# 3_0.net
KiCad netlist of a schematic drawn in EasyEDA Pro
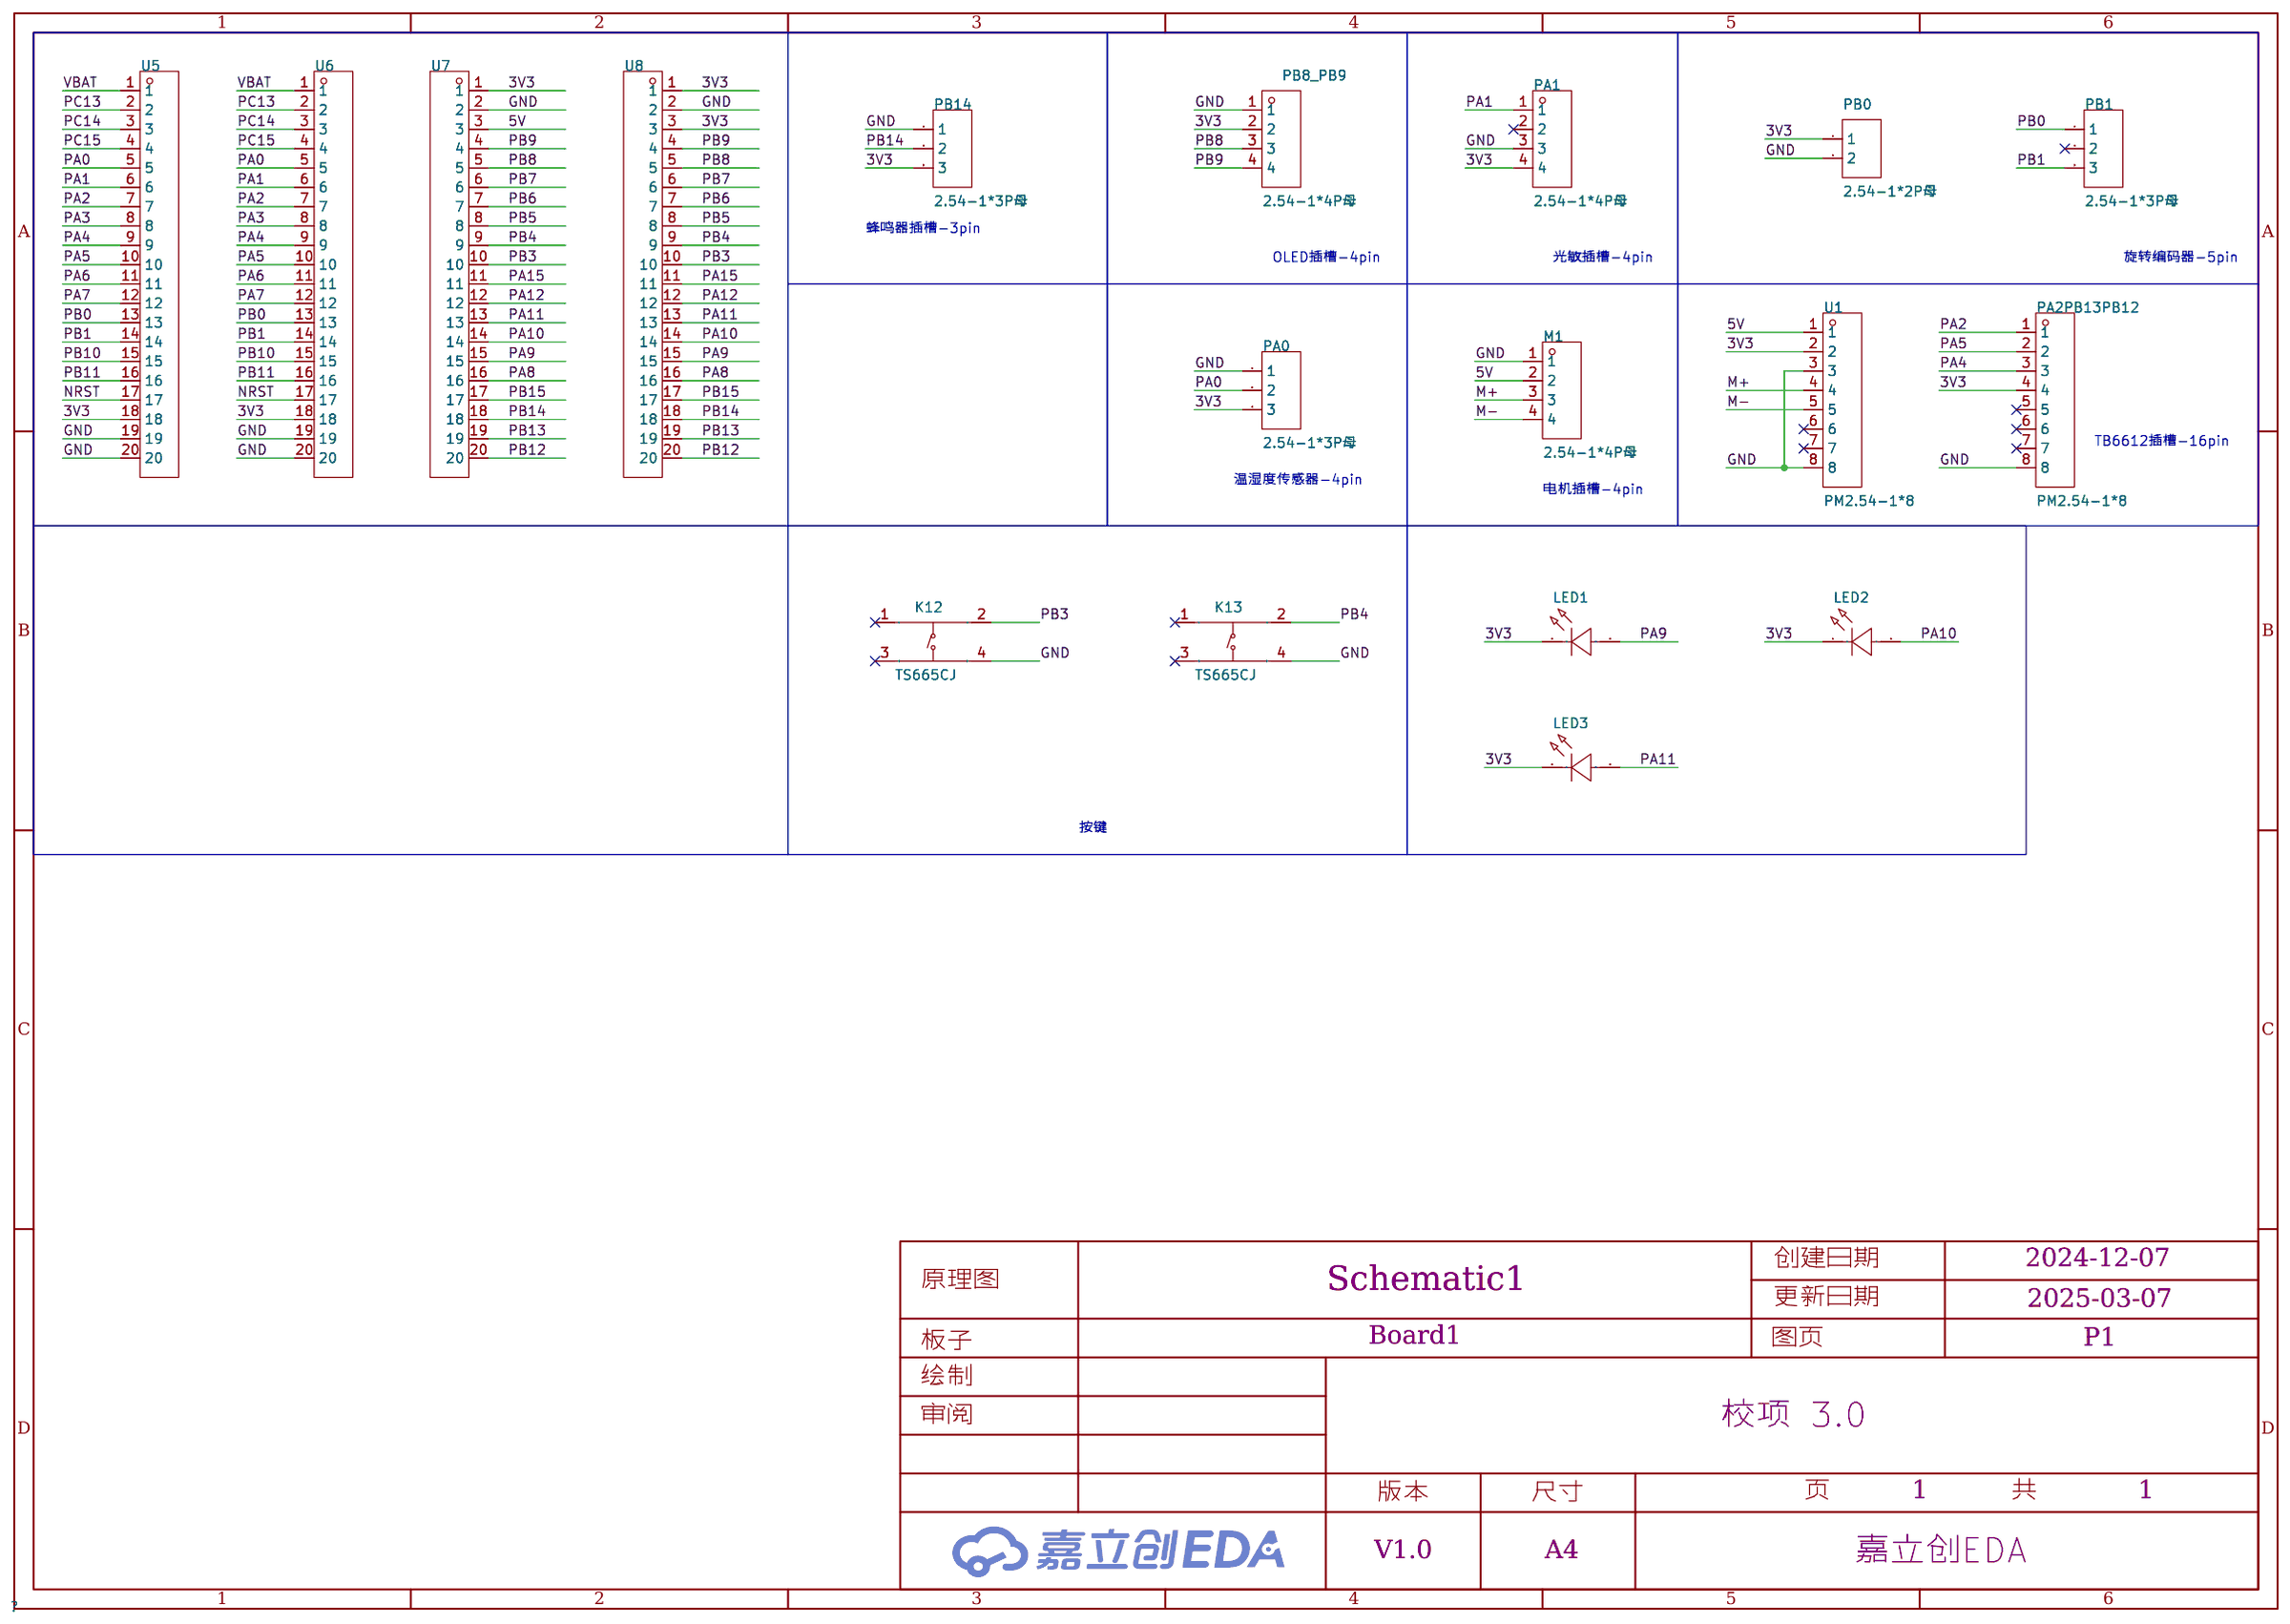
[diagram p0: schematic sheet]

(export (version "E")
  (design (tool "Eeschema 10.0.6"))
  (components
    (comp (ref "K12")
      (value "TS665CJ")
      (footprint "easyedapro:SW-TH_4P-L6.0-W6.0-P4.50-LS6.5")
      (description "电路结构:单刀单掷;按钮形状:圆形按钮;安装方式:直插;开关长度:6mm;开关宽度:6mm;开关高度:5mm;触点电流:50mA;额定电压(DC):12V;带灯:-;机械寿命:-;")
      (fields (field (name "Manufacturer") "SHOU HAN(首韩)"))
      (libsource (lib "easyedapro") (part "TS665CJ"))
    )
    (comp (ref "K13")
      (value "TS665CJ")
      (footprint "easyedapro:SW-TH_4P-L6.0-W6.0-P4.50-LS6.5")
      (description "电路结构:单刀单掷;按钮形状:圆形按钮;安装方式:直插;开关长度:6mm;开关宽度:6mm;开关高度:5mm;触点电流:50mA;额定电压(DC):12V;带灯:-;机械寿命:-;")
      (fields (field (name "Manufacturer") "SHOU HAN(首韩)"))
      (libsource (lib "easyedapro") (part "TS665CJ"))
    )
    (comp (ref "LED1")
      (value "NFD5408BC")
      (footprint "easyedapro:LED-TH_BD5.7-P2.54-RD")
      (description "发光颜色:蓝色;功率:200mW;主波长:460nm~470nm;发光角度:20°;工作温度:-30°C~+85°C;")
      (fields (field (name "Manufacturer") "国星光电"))
      (libsource (lib "easyedapro") (part "NFD5408BC"))
    )
    (comp (ref "LED2")
      (value "NFD5408BC")
      (footprint "easyedapro:LED-TH_BD5.7-P2.54-RD")
      (description "发光颜色:蓝色;功率:200mW;主波长:460nm~470nm;发光角度:20°;工作温度:-30°C~+85°C;")
      (fields (field (name "Manufacturer") "国星光电"))
      (libsource (lib "easyedapro") (part "NFD5408BC"))
    )
    (comp (ref "LED3")
      (value "NFD5408BC")
      (footprint "easyedapro:LED-TH_BD5.7-P2.54-RD")
      (description "发光颜色:蓝色;功率:200mW;主波长:460nm~470nm;发光角度:20°;工作温度:-30°C~+85°C;")
      (fields (field (name "Manufacturer") "国星光电"))
      (libsource (lib "easyedapro") (part "NFD5408BC"))
    )
    (comp (ref "M1")
      (value "2.54-1*4P母")
      (footprint "easyedapro:HDR-TH_4P-P2.54-V-F")
      (fields (field (name "Manufacturer") "BOOMELE(博穆精密)"))
      (libsource (lib "easyedapro") (part "2.54-1*4P母"))
    )
    (comp (ref "PA0")
      (value "2.54-1*3P母")
      (footprint "easyedapro:HDR-TH_3P-P2.54-V-F")
      (description "间距:2.54mm;行距:-;安装类型:直插;排数:单排;总孔位数:3P;塑高:-;触头材质:-;触头镀层:金;")
      (fields (field (name "Manufacturer") "BOOMELE(博穆精密)"))
      (libsource (lib "easyedapro") (part "Header-Female-2.54_1x3"))
    )
    (comp (ref "PA1")
      (value "2.54-1*4P母")
      (footprint "easyedapro:HDR-TH_4P-P2.54-V-F")
      (fields (field (name "Manufacturer") "BOOMELE(博穆精密)"))
      (libsource (lib "easyedapro") (part "2.54-1*4P母"))
    )
    (comp (ref "PA2PB13PB12")
      (value "PM2.54-1*8")
      (footprint "easyedapro:HDR-TH_8P-P2.54-V-F")
      (fields (field (name "Manufacturer") "ZHOURI(洲日)"))
      (libsource (lib "easyedapro") (part "PM2.54-1*8"))
    )
    (comp (ref "PB0")
      (value "2.54-1*2P母")
      (footprint "easyedapro:HDR-TH_2P-P2.54-V-F")
      (description "插孔结构:1x2P;间距:2.54mm;行距:-;安装类型:直插;排数:单排;总孔位数:2P;塑高:-;触头材质:-;触头镀层:-;")
      (fields (field (name "Manufacturer") "BOOMELE(博穆精密)"))
      (libsource (lib "easyedapro") (part "Header-Female-2.54_1x2"))
    )
    (comp (ref "PB1")
      (value "2.54-1*3P母")
      (footprint "easyedapro:HDR-TH_3P-P2.54-V-F")
      (description "间距:2.54mm;行距:-;安装类型:直插;排数:单排;总孔位数:3P;塑高:-;触头材质:-;触头镀层:金;")
      (fields (field (name "Manufacturer") "BOOMELE(博穆精密)"))
      (libsource (lib "easyedapro") (part "Header-Female-2.54_1x3"))
    )
    (comp (ref "PB8_PB9")
      (value "2.54-1*4P母")
      (footprint "easyedapro:HDR-TH_4P-P2.54-V-F")
      (fields (field (name "Manufacturer") "BOOMELE(博穆精密)"))
      (libsource (lib "easyedapro") (part "2.54-1*4P母"))
    )
    (comp (ref "PB14")
      (value "2.54-1*3P母")
      (footprint "easyedapro:HDR-TH_3P-P2.54-V-F")
      (description "间距:2.54mm;行距:-;安装类型:直插;排数:单排;总孔位数:3P;塑高:-;触头材质:-;触头镀层:金;")
      (fields (field (name "Manufacturer") "BOOMELE(博穆精密)"))
      (libsource (lib "easyedapro") (part "Header-Female-2.54_1x3"))
    )
    (comp (ref "U1")
      (value "PM2.54-1*8")
      (footprint "easyedapro:HDR-TH_8P-P2.54-V-F")
      (fields (field (name "Manufacturer") "ZHOURI(洲日)"))
      (libsource (lib "easyedapro") (part "PM2.54-1*8"))
    )
    (comp (ref "U5")
      (value "KH-2.54FH-1X20P-H8.5")
      (footprint "easyedapro:HDR-TH_20P-P2.54-V-F-2")
      (fields (field (name "Manufacturer") "kinghelm(金航标)"))
      (libsource (lib "easyedapro") (part "KH-2.54FH-1X20P-H8.5"))
    )
    (comp (ref "U6")
      (value "KH-2.54FH-1X20P-H8.5")
      (footprint "easyedapro:HDR-TH_20P-P2.54-V-F-2")
      (fields (field (name "Manufacturer") "kinghelm(金航标)"))
      (libsource (lib "easyedapro") (part "KH-2.54FH-1X20P-H8.5"))
    )
    (comp (ref "U7")
      (value "KH-2.54FH-1X20P-H8.5")
      (footprint "easyedapro:HDR-TH_20P-P2.54-V-F-2")
      (fields (field (name "Manufacturer") "kinghelm(金航标)"))
      (libsource (lib "easyedapro") (part "KH-2.54FH-1X20P-H8.5"))
    )
    (comp (ref "U8")
      (value "KH-2.54FH-1X20P-H8.5")
      (footprint "easyedapro:HDR-TH_20P-P2.54-V-F-2")
      (fields (field (name "Manufacturer") "kinghelm(金航标)"))
      (libsource (lib "easyedapro") (part "KH-2.54FH-1X20P-H8.5"))
    )
  )
  (nets
    (net (code "1") (name "/3V3") (class "Default")
      (node (ref "LED1") (pin "1") (pinfunction "K_1") (pintype "unspecified"))
      (node (ref "LED2") (pin "1") (pinfunction "K_1") (pintype "unspecified"))
      (node (ref "LED3") (pin "1") (pinfunction "K_1") (pintype "unspecified"))
      (node (ref "PA0") (pin "3") (pinfunction "3_3") (pintype "input"))
      (node (ref "PA1") (pin "4") (pinfunction "4_4") (pintype "unspecified"))
      (node (ref "PA2PB13PB12") (pin "4") (pinfunction "4_4") (pintype "unspecified"))
      (node (ref "PB0") (pin "1") (pinfunction "1_1") (pintype "input"))
      (node (ref "PB14") (pin "3") (pinfunction "3_3") (pintype "input"))
      (node (ref "PB8_PB9") (pin "2") (pinfunction "2_2") (pintype "unspecified"))
      (node (ref "U1") (pin "2") (pinfunction "2_2") (pintype "unspecified"))
      (node (ref "U5") (pin "18") (pinfunction "18_18") (pintype "unspecified"))
      (node (ref "U6") (pin "18") (pinfunction "18_18") (pintype "unspecified"))
      (node (ref "U7") (pin "1") (pinfunction "1_1") (pintype "unspecified"))
      (node (ref "U8") (pin "1") (pinfunction "1_1") (pintype "unspecified"))
      (node (ref "U8") (pin "3") (pinfunction "3_3") (pintype "unspecified"))
    )
    (net (code "2") (name "/5V") (class "Default")
      (node (ref "M1") (pin "2") (pinfunction "2_2") (pintype "unspecified"))
      (node (ref "U1") (pin "1") (pinfunction "1_1") (pintype "unspecified"))
      (node (ref "U7") (pin "3") (pinfunction "3_3") (pintype "unspecified"))
    )
    (net (code "3") (name "/GND") (class "Default")
      (node (ref "K12") (pin "4") (pinfunction "D_4") (pintype "unspecified"))
      (node (ref "K13") (pin "4") (pinfunction "D_4") (pintype "unspecified"))
      (node (ref "M1") (pin "1") (pinfunction "1_1") (pintype "unspecified"))
      (node (ref "PA0") (pin "1") (pinfunction "1_1") (pintype "input"))
      (node (ref "PA1") (pin "3") (pinfunction "3_3") (pintype "unspecified"))
      (node (ref "PA2PB13PB12") (pin "8") (pinfunction "8_8") (pintype "unspecified"))
      (node (ref "PB0") (pin "2") (pinfunction "2_2") (pintype "input"))
      (node (ref "PB14") (pin "1") (pinfunction "1_1") (pintype "input"))
      (node (ref "PB8_PB9") (pin "1") (pinfunction "1_1") (pintype "unspecified"))
      (node (ref "U1") (pin "3") (pinfunction "3_3") (pintype "unspecified"))
      (node (ref "U1") (pin "8") (pinfunction "8_8") (pintype "unspecified"))
      (node (ref "U5") (pin "19") (pinfunction "19_19") (pintype "unspecified"))
      (node (ref "U5") (pin "20") (pinfunction "20_20") (pintype "unspecified"))
      (node (ref "U6") (pin "19") (pinfunction "19_19") (pintype "unspecified"))
      (node (ref "U6") (pin "20") (pinfunction "20_20") (pintype "unspecified"))
      (node (ref "U7") (pin "2") (pinfunction "2_2") (pintype "unspecified"))
      (node (ref "U8") (pin "2") (pinfunction "2_2") (pintype "unspecified"))
    )
    (net (code "4") (name "/M+") (class "Default")
      (node (ref "M1") (pin "3") (pinfunction "3_3") (pintype "unspecified"))
      (node (ref "U1") (pin "4") (pinfunction "4_4") (pintype "unspecified"))
    )
    (net (code "5") (name "/M-") (class "Default")
      (node (ref "M1") (pin "4") (pinfunction "4_4") (pintype "unspecified"))
      (node (ref "U1") (pin "5") (pinfunction "5_5") (pintype "unspecified"))
    )
    (net (code "6") (name "/NRST") (class "Default")
      (node (ref "U5") (pin "17") (pinfunction "17_17") (pintype "unspecified"))
      (node (ref "U6") (pin "17") (pinfunction "17_17") (pintype "unspecified"))
    )
    (net (code "7") (name "/PA0") (class "Default")
      (node (ref "PA0") (pin "2") (pinfunction "2_2") (pintype "input"))
      (node (ref "U5") (pin "5") (pinfunction "5_5") (pintype "unspecified"))
      (node (ref "U6") (pin "5") (pinfunction "5_5") (pintype "unspecified"))
    )
    (net (code "8") (name "/PA1") (class "Default")
      (node (ref "PA1") (pin "1") (pinfunction "1_1") (pintype "unspecified"))
      (node (ref "U5") (pin "6") (pinfunction "6_6") (pintype "unspecified"))
      (node (ref "U6") (pin "6") (pinfunction "6_6") (pintype "unspecified"))
    )
    (net (code "9") (name "/PA2") (class "Default")
      (node (ref "PA2PB13PB12") (pin "1") (pinfunction "1_1") (pintype "unspecified"))
      (node (ref "U5") (pin "7") (pinfunction "7_7") (pintype "unspecified"))
      (node (ref "U6") (pin "7") (pinfunction "7_7") (pintype "unspecified"))
    )
    (net (code "10") (name "/PA3") (class "Default")
      (node (ref "U5") (pin "8") (pinfunction "8_8") (pintype "unspecified"))
      (node (ref "U6") (pin "8") (pinfunction "8_8") (pintype "unspecified"))
    )
    (net (code "11") (name "/PA4") (class "Default")
      (node (ref "PA2PB13PB12") (pin "3") (pinfunction "3_3") (pintype "unspecified"))
      (node (ref "U5") (pin "9") (pinfunction "9_9") (pintype "unspecified"))
      (node (ref "U6") (pin "9") (pinfunction "9_9") (pintype "unspecified"))
    )
    (net (code "12") (name "/PA5") (class "Default")
      (node (ref "PA2PB13PB12") (pin "2") (pinfunction "2_2") (pintype "unspecified"))
      (node (ref "U5") (pin "10") (pinfunction "10_10") (pintype "unspecified"))
      (node (ref "U6") (pin "10") (pinfunction "10_10") (pintype "unspecified"))
    )
    (net (code "13") (name "/PA6") (class "Default")
      (node (ref "U5") (pin "11") (pinfunction "11_11") (pintype "unspecified"))
      (node (ref "U6") (pin "11") (pinfunction "11_11") (pintype "unspecified"))
    )
    (net (code "14") (name "/PA7") (class "Default")
      (node (ref "U5") (pin "12") (pinfunction "12_12") (pintype "unspecified"))
      (node (ref "U6") (pin "12") (pinfunction "12_12") (pintype "unspecified"))
    )
    (net (code "15") (name "/PA8") (class "Default")
      (node (ref "U7") (pin "16") (pinfunction "16_16") (pintype "unspecified"))
      (node (ref "U8") (pin "16") (pinfunction "16_16") (pintype "unspecified"))
    )
    (net (code "16") (name "/PA9") (class "Default")
      (node (ref "LED1") (pin "2") (pinfunction "A_2") (pintype "unspecified"))
      (node (ref "U7") (pin "15") (pinfunction "15_15") (pintype "unspecified"))
      (node (ref "U8") (pin "15") (pinfunction "15_15") (pintype "unspecified"))
    )
    (net (code "17") (name "/PA10") (class "Default")
      (node (ref "LED2") (pin "2") (pinfunction "A_2") (pintype "unspecified"))
      (node (ref "U7") (pin "14") (pinfunction "14_14") (pintype "unspecified"))
      (node (ref "U8") (pin "14") (pinfunction "14_14") (pintype "unspecified"))
    )
    (net (code "18") (name "/PA11") (class "Default")
      (node (ref "LED3") (pin "2") (pinfunction "A_2") (pintype "unspecified"))
      (node (ref "U7") (pin "13") (pinfunction "13_13") (pintype "unspecified"))
      (node (ref "U8") (pin "13") (pinfunction "13_13") (pintype "unspecified"))
    )
    (net (code "19") (name "/PA12") (class "Default")
      (node (ref "U7") (pin "12") (pinfunction "12_12") (pintype "unspecified"))
      (node (ref "U8") (pin "12") (pinfunction "12_12") (pintype "unspecified"))
    )
    (net (code "20") (name "/PA15") (class "Default")
      (node (ref "U7") (pin "11") (pinfunction "11_11") (pintype "unspecified"))
      (node (ref "U8") (pin "11") (pinfunction "11_11") (pintype "unspecified"))
    )
    (net (code "21") (name "/PB0") (class "Default")
      (node (ref "PB1") (pin "1") (pinfunction "1_1") (pintype "input"))
      (node (ref "U5") (pin "13") (pinfunction "13_13") (pintype "unspecified"))
      (node (ref "U6") (pin "13") (pinfunction "13_13") (pintype "unspecified"))
    )
    (net (code "22") (name "/PB1") (class "Default")
      (node (ref "PB1") (pin "3") (pinfunction "3_3") (pintype "input"))
      (node (ref "U5") (pin "14") (pinfunction "14_14") (pintype "unspecified"))
      (node (ref "U6") (pin "14") (pinfunction "14_14") (pintype "unspecified"))
    )
    (net (code "23") (name "/PB3") (class "Default")
      (node (ref "K12") (pin "2") (pinfunction "B_2") (pintype "unspecified"))
      (node (ref "U7") (pin "10") (pinfunction "10_10") (pintype "unspecified"))
      (node (ref "U8") (pin "10") (pinfunction "10_10") (pintype "unspecified"))
    )
    (net (code "24") (name "/PB4") (class "Default")
      (node (ref "K13") (pin "2") (pinfunction "B_2") (pintype "unspecified"))
      (node (ref "U7") (pin "9") (pinfunction "9_9") (pintype "unspecified"))
      (node (ref "U8") (pin "9") (pinfunction "9_9") (pintype "unspecified"))
    )
    (net (code "25") (name "/PB5") (class "Default")
      (node (ref "U7") (pin "8") (pinfunction "8_8") (pintype "unspecified"))
      (node (ref "U8") (pin "8") (pinfunction "8_8") (pintype "unspecified"))
    )
    (net (code "26") (name "/PB6") (class "Default")
      (node (ref "U7") (pin "7") (pinfunction "7_7") (pintype "unspecified"))
      (node (ref "U8") (pin "7") (pinfunction "7_7") (pintype "unspecified"))
    )
    (net (code "27") (name "/PB7") (class "Default")
      (node (ref "U7") (pin "6") (pinfunction "6_6") (pintype "unspecified"))
      (node (ref "U8") (pin "6") (pinfunction "6_6") (pintype "unspecified"))
    )
    (net (code "28") (name "/PB8") (class "Default")
      (node (ref "PB8_PB9") (pin "3") (pinfunction "3_3") (pintype "unspecified"))
      (node (ref "U7") (pin "5") (pinfunction "5_5") (pintype "unspecified"))
      (node (ref "U8") (pin "5") (pinfunction "5_5") (pintype "unspecified"))
    )
    (net (code "29") (name "/PB9") (class "Default")
      (node (ref "PB8_PB9") (pin "4") (pinfunction "4_4") (pintype "unspecified"))
      (node (ref "U7") (pin "4") (pinfunction "4_4") (pintype "unspecified"))
      (node (ref "U8") (pin "4") (pinfunction "4_4") (pintype "unspecified"))
    )
    (net (code "30") (name "/PB10") (class "Default")
      (node (ref "U5") (pin "15") (pinfunction "15_15") (pintype "unspecified"))
      (node (ref "U6") (pin "15") (pinfunction "15_15") (pintype "unspecified"))
    )
    (net (code "31") (name "/PB11") (class "Default")
      (node (ref "U5") (pin "16") (pinfunction "16_16") (pintype "unspecified"))
      (node (ref "U6") (pin "16") (pinfunction "16_16") (pintype "unspecified"))
    )
    (net (code "32") (name "/PB12") (class "Default")
      (node (ref "U7") (pin "20") (pinfunction "20_20") (pintype "unspecified"))
      (node (ref "U8") (pin "20") (pinfunction "20_20") (pintype "unspecified"))
    )
    (net (code "33") (name "/PB13") (class "Default")
      (node (ref "U7") (pin "19") (pinfunction "19_19") (pintype "unspecified"))
      (node (ref "U8") (pin "19") (pinfunction "19_19") (pintype "unspecified"))
    )
    (net (code "34") (name "/PB14") (class "Default")
      (node (ref "PB14") (pin "2") (pinfunction "2_2") (pintype "input"))
      (node (ref "U7") (pin "18") (pinfunction "18_18") (pintype "unspecified"))
      (node (ref "U8") (pin "18") (pinfunction "18_18") (pintype "unspecified"))
    )
    (net (code "35") (name "/PB15") (class "Default")
      (node (ref "U7") (pin "17") (pinfunction "17_17") (pintype "unspecified"))
      (node (ref "U8") (pin "17") (pinfunction "17_17") (pintype "unspecified"))
    )
    (net (code "36") (name "/PC13") (class "Default")
      (node (ref "U5") (pin "2") (pinfunction "2_2") (pintype "unspecified"))
      (node (ref "U6") (pin "2") (pinfunction "2_2") (pintype "unspecified"))
    )
    (net (code "37") (name "/PC14") (class "Default")
      (node (ref "U5") (pin "3") (pinfunction "3_3") (pintype "unspecified"))
      (node (ref "U6") (pin "3") (pinfunction "3_3") (pintype "unspecified"))
    )
    (net (code "38") (name "/PC15") (class "Default")
      (node (ref "U5") (pin "4") (pinfunction "4_4") (pintype "unspecified"))
      (node (ref "U6") (pin "4") (pinfunction "4_4") (pintype "unspecified"))
    )
    (net (code "39") (name "/VBAT") (class "Default")
      (node (ref "U5") (pin "1") (pinfunction "1_1") (pintype "unspecified"))
      (node (ref "U6") (pin "1") (pinfunction "1_1") (pintype "unspecified"))
    )
    (net (code "40") (name "unconnected-(K12-A-Pad1)") (class "Default")
      (node (ref "K12") (pin "1") (pinfunction "A_1") (pintype "unspecified+no_connect"))
    )
    (net (code "41") (name "unconnected-(K12-C-Pad3)") (class "Default")
      (node (ref "K12") (pin "3") (pinfunction "C_3") (pintype "unspecified+no_connect"))
    )
    (net (code "42") (name "unconnected-(K13-A-Pad1)") (class "Default")
      (node (ref "K13") (pin "1") (pinfunction "A_1") (pintype "unspecified+no_connect"))
    )
    (net (code "43") (name "unconnected-(K13-C-Pad3)") (class "Default")
      (node (ref "K13") (pin "3") (pinfunction "C_3") (pintype "unspecified+no_connect"))
    )
    (net (code "44") (name "unconnected-(PA1-Pad2)") (class "Default")
      (node (ref "PA1") (pin "2") (pinfunction "2_2") (pintype "unspecified+no_connect"))
    )
    (net (code "45") (name "unconnected-(PA2PB13PB12-Pad5)") (class "Default")
      (node (ref "PA2PB13PB12") (pin "5") (pinfunction "5_5") (pintype "unspecified+no_connect"))
    )
    (net (code "46") (name "unconnected-(PA2PB13PB12-Pad6)") (class "Default")
      (node (ref "PA2PB13PB12") (pin "6") (pinfunction "6_6") (pintype "unspecified+no_connect"))
    )
    (net (code "47") (name "unconnected-(PA2PB13PB12-Pad7)") (class "Default")
      (node (ref "PA2PB13PB12") (pin "7") (pinfunction "7_7") (pintype "unspecified+no_connect"))
    )
    (net (code "48") (name "unconnected-(PB1-Pad2)") (class "Default")
      (node (ref "PB1") (pin "2") (pinfunction "2_2") (pintype "input+no_connect"))
    )
    (net (code "49") (name "unconnected-(U1-Pad6)") (class "Default")
      (node (ref "U1") (pin "6") (pinfunction "6_6") (pintype "unspecified+no_connect"))
    )
    (net (code "50") (name "unconnected-(U1-Pad7)") (class "Default")
      (node (ref "U1") (pin "7") (pinfunction "7_7") (pintype "unspecified+no_connect"))
    )
  )
)
